# OutputDriver.net
KiCad netlist of a schematic drawn in Altium Designer
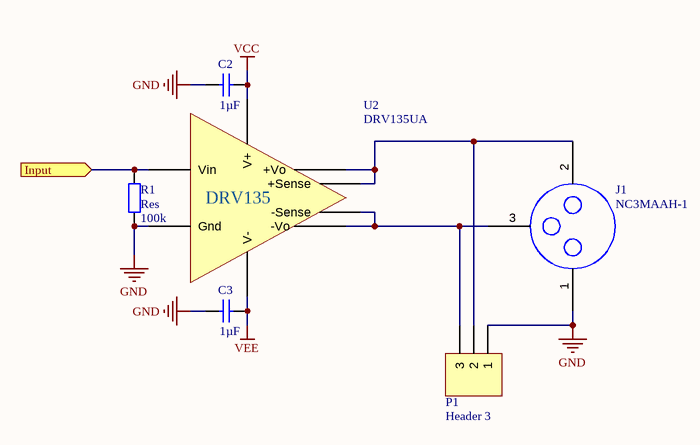
[diagram p0: OutputDriver.SchDoc]

(export (version "E")
  (design (tool "Eeschema 10.0.6"))
  (components
    (comp (ref "C2")
      (value "1µF")
      (footprint "CAPC3225N")
      (description "Chip cap 1uF 50v X7R 1210")
      (fields (field (name "TOLERANCE") "10%") (field (name "ZENITEL PARTNUMBER") "4000084277"))
      (libsource (lib "Zenitel Concord PRO Vault") (part "Capacitor-IEC"))
    )
    (comp (ref "C3")
      (value "1µF")
      (footprint "CAPC3225N")
      (description "Chip cap 1uF 50v X7R 1210")
      (fields (field (name "TOLERANCE") "10%") (field (name "ZENITEL PARTNUMBER") "4000084277"))
      (libsource (lib "Zenitel Concord PRO Vault") (part "Capacitor-IEC"))
    )
    (comp (ref "J1")
      (value "NC3MAAH-1")
      (footprint "NC3MAAH-1")
      (description "NC3MAAH-1 3pole male XLR 90deg")
      (fields (field (name "ZENITEL PARTNUMBER") "4000083185"))
      (libsource (lib "Zenitel Concord PRO Vault") (part "NC3MAAH-1"))
    )
    (comp (ref "P1")
      (value "Header 3")
      (footprint "MTA-100-3P")
      (description "MTA-100-3P 3-pin header")
      (fields (field (name "ZENITEL PARTNUMBER") "4000085467"))
      (libsource (lib "Zenitel Concord PRO Vault") (part "Header 3"))
    )
    (comp (ref "R1")
      (value "Res")
      (footprint "RESC1005X40X25NL05T05")
      (description "Chip resistor 100K - 0402")
      (fields
        (field (name "ALTIUM_VALUE") "100k")
        (field (name "POWER") "62.5mW")
        (field (name "ZENITEL PARTNUMBER") "4000081112")
      )
      (libsource (lib "Zenitel Concord PRO Vault") (part "Resistor-IEC"))
    )
    (comp (ref "U2")
      (value "DRV135UA")
      (footprint "SOIC127P600X360-8N")
      (description "Audio Amplifiers AUDIO LINE DRIVERS")
      (fields (field (name "VOLTAGE") "18V"))
      (libsource (lib "Zenitel Concord PRO Vault") (part "DRV135UA"))
    )
  )
  (nets
    (net (code "1") (name "/Input") (class "Default")
      (node (ref "R1") (pin "2") (pinfunction "2_2") (pintype "passive"))
      (node (ref "U2") (pin "4") (pinfunction "Vin_4") (pintype "passive"))
    )
    (net (code "2") (name "GND") (class "Default")
      (node (ref "C2") (pin "1") (pinfunction "1_1") (pintype "passive"))
      (node (ref "C3") (pin "1") (pinfunction "1_1") (pintype "passive"))
      (node (ref "J1") (pin "1") (pinfunction "1_1") (pintype "passive"))
      (node (ref "P1") (pin "1") (pinfunction "1_1") (pintype "passive"))
      (node (ref "R1") (pin "1") (pinfunction "1_1") (pintype "passive"))
      (node (ref "U2") (pin "3") (pinfunction "Gnd_3") (pintype "passive"))
    )
    (net (code "3") (name "Net-(U2-+Sense)") (class "Default")
      (node (ref "J1") (pin "2") (pinfunction "2_2") (pintype "passive"))
      (node (ref "P1") (pin "2") (pinfunction "2_2") (pintype "passive"))
      (node (ref "U2") (pin "7") (pinfunction "+Sense_7") (pintype "passive"))
      (node (ref "U2") (pin "8") (pinfunction "+Vo_8") (pintype "passive"))
    )
    (net (code "4") (name "Net-(U2--Sense)") (class "Default")
      (node (ref "J1") (pin "3") (pinfunction "3_3") (pintype "passive"))
      (node (ref "P1") (pin "3") (pinfunction "3_3") (pintype "passive"))
      (node (ref "U2") (pin "1") (pinfunction "-Vo_1") (pintype "passive"))
      (node (ref "U2") (pin "2") (pinfunction "-Sense_2") (pintype "passive"))
    )
    (net (code "5") (name "VCC") (class "Default")
      (node (ref "C2") (pin "2") (pinfunction "2_2") (pintype "passive"))
      (node (ref "U2") (pin "6") (pinfunction "V+_6") (pintype "passive"))
    )
    (net (code "6") (name "VEE") (class "Default")
      (node (ref "C3") (pin "2") (pinfunction "2_2") (pintype "passive"))
      (node (ref "U2") (pin "5") (pinfunction "V-_5") (pintype "passive"))
    )
  )
)
